# design.net
KiCad netlist of a schematic drawn in Altium Designer
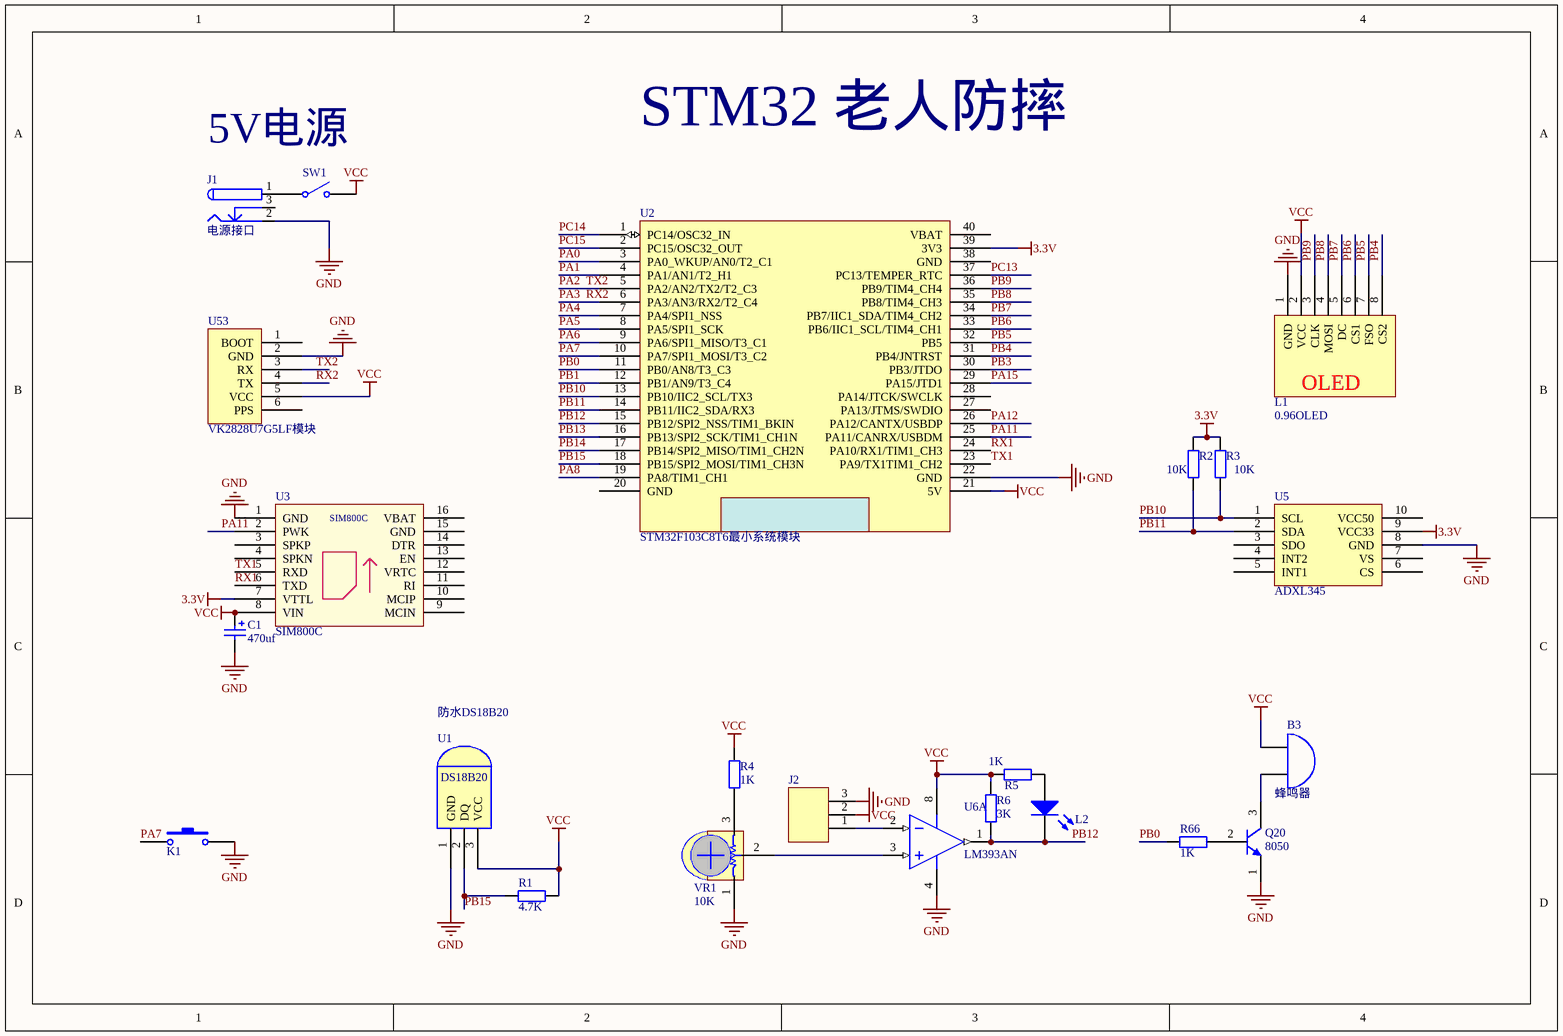
[diagram p0: 原理图.SchDoc]

(export (version "E")
  (design (tool "Eeschema 10.0.6"))
  (components
    (comp (ref "B3")
      (value "蜂鸣器")
      (footprint "Buzzy-Small")
      (description "Electrical Bell")
      (fields (field (name "PUBLISHER") "Altium Limited"))
      (libsource (lib "YANG") (part "Bell"))
    )
    (comp (ref "C1") (value "470uf") (footprint "CD5.08cm-10*16-M") (libsource (lib "电容") (part "Cap Pol")))
    (comp (ref "J1")
      (value "电源接口")
      (footprint "DC-JACK")
      (description "Low Voltage Power Supply Connector")
      (fields (field (name "PUBLISHER") "Altium Limited"))
      (libsource (lib "Miscellaneous Connectors") (part "PWR2.5"))
    )
    (comp (ref "J2") (value "~") (footprint "3ZHEN-100mil") (libsource (lib "元件") (part "H3")))
    (comp (ref "K1") (value "SW-AJ") (footprint "sw-6-6") (libsource (lib "YANG") (part "SW-AJ")))
    (comp (ref "L1") (value "0.96OLED") (footprint "OLED_0.96") (libsource (lib "万年历") (part "OLED_0.96")))
    (comp (ref "L2") (value "LED") (footprint "LED-3") (libsource (lib "YANG") (part "LED")))
    (comp (ref "Q20") (value "8050") (footprint "TO-92-2N3906") (libsource (lib "32") (part "8050")))
    (comp (ref "R1")
      (value "4.7K")
      (footprint "AXIAL-0.3")
      (description "Resistor")
      (libsource (lib "20170808毕业设计模块资料整理") (part "Res2"))
    )
    (comp (ref "R2") (value "10K") (footprint "AXIAL-0.3") (libsource (lib "YANG") (part "RES0.2")))
    (comp (ref "R3") (value "10K") (footprint "AXIAL-0.3") (libsource (lib "YANG") (part "RES0.2")))
    (comp (ref "R4")
      (value "1k")
      (footprint "AXIAL-0.3")
      (fields (field (name "ALTIUM_UNNAMED_1") "1K"))
      (libsource (lib "") (part "RES0.2_1"))
    )
    (comp (ref "R5") (value "1K") (footprint "AXIAL-0.3") (libsource (lib "YANG") (part "RES0.4")))
    (comp (ref "R6")
      (value "3k")
      (footprint "AXIAL-0.3")
      (fields (field (name "ALTIUM_UNNAMED_1") "3K"))
      (libsource (lib "") (part "RES0.2_1"))
    )
    (comp (ref "R66")
      (value "1K")
      (footprint "AXIAL-0.3")
      (description "Resistor")
      (libsource (lib "20170808毕业设计模块资料整理") (part "Res2"))
    )
    (comp (ref "SW1") (value "自锁开关") (footprint "SW1") (libsource (lib "各种开关") (part "SW-SPST")))
    (comp (ref "U1")
      (value "防水DS18B20")
      (footprint "DS18b20")
      (libsource (lib "20170808毕业设计模块资料整理") (part "DS18B20"))
    )
    (comp (ref "U2")
      (value "STM32F103C8T6最小系统模块")
      (footprint "STM32F103C8T6最下系统模块")
      (libsource (lib "32") (part "STM32F103C8T6最下系统模块"))
    )
    (comp (ref "U3") (value "SIM800C") (footprint "SIM800C") (libsource (lib "PCB_Project") (part "SIM800C")))
    (comp (ref "U5") (value "ADXL345") (footprint "ADXL345") (libsource (lib "原理图") (part "ADXL345")))
    (comp (ref "U6")
      (value "LM393AN")
      (footprint "DIP8")
      (description "Dual Comparator")
      (fields (field (name "PUBLISHER") "Altium Limited"))
      (libsource (lib "Motorola Analog Comparator") (part "LM393AN"))
    )
    (comp (ref "U53")
      (value "VK2828U7G5LF模块")
      (footprint "HDR1X6H")
      (libsource (lib "20170808毕业设计模块资料整理") (part "gps"))
    )
    (comp (ref "VR1")
      (value "10K")
      (footprint "W2")
      (libsource (lib "毕业设计模块资料SCH_Library. (1)") (part "电位器-蓝白"))
    )
  )
  (nets
    (net (code "1") (name "/PA0") (class "Default")
      (node (ref "U2") (pin "3") (pinfunction "PA0_WKUP/AN0/T2_C1_3") (pintype "passive"))
    )
    (net (code "2") (name "/PA1") (class "Default")
      (node (ref "U2") (pin "4") (pinfunction "PA1/AN1/T2_H1_4") (pintype "passive"))
    )
    (net (code "3") (name "/PA2") (class "Default")
      (node (ref "U2") (pin "5") (pinfunction "PA2/AN2/TX2/T2_C3_5") (pintype "passive"))
      (node (ref "U53") (pin "3") (pinfunction "RX_3") (pintype "passive"))
    )
    (net (code "4") (name "/PA3") (class "Default")
      (node (ref "U2") (pin "6") (pinfunction "PA3/AN3/RX2/T2_C4_6") (pintype "passive"))
      (node (ref "U53") (pin "4") (pinfunction "TX_4") (pintype "passive"))
    )
    (net (code "5") (name "/PA4") (class "Default")
      (node (ref "U2") (pin "7") (pinfunction "PA4/SPI1_NSS_7") (pintype "passive"))
    )
    (net (code "6") (name "/PA5") (class "Default")
      (node (ref "U2") (pin "8") (pinfunction "PA5/SPI1_SCK_8") (pintype "passive"))
    )
    (net (code "7") (name "/PA6") (class "Default")
      (node (ref "U2") (pin "9") (pinfunction "PA6/SPI1_MISO/T3_C1_9") (pintype "passive"))
    )
    (net (code "8") (name "/PA7") (class "Default")
      (node (ref "K1") (pin "1") (pinfunction "1_1") (pintype "passive"))
      (node (ref "U2") (pin "10") (pinfunction "PA7/SPI1_MOSI/T3_C2_10") (pintype "passive"))
    )
    (net (code "9") (name "/PA8") (class "Default")
      (node (ref "U2") (pin "19") (pinfunction "PA8/TIM1_CH1_19") (pintype "passive"))
    )
    (net (code "10") (name "/PA11") (class "Default")
      (node (ref "U2") (pin "25") (pinfunction "PA11/CANRX/USBDM_25") (pintype "passive"))
      (node (ref "U3") (pin "2") (pinfunction "PWK_2") (pintype "passive"))
    )
    (net (code "11") (name "/PA12") (class "Default")
      (node (ref "U2") (pin "26") (pinfunction "PA12/CANTX/USBDP_26") (pintype "passive"))
    )
    (net (code "12") (name "/PA15") (class "Default")
      (node (ref "U2") (pin "29") (pinfunction "PA15/JTD1_29") (pintype "passive"))
    )
    (net (code "13") (name "/PB0") (class "Default")
      (node (ref "R66") (pin "1") (pinfunction "1_1") (pintype "passive"))
      (node (ref "U2") (pin "11") (pinfunction "PB0/AN8/T3_C3_11") (pintype "passive"))
    )
    (net (code "14") (name "/PB1") (class "Default")
      (node (ref "U2") (pin "12") (pinfunction "PB1/AN9/T3_C4_12") (pintype "passive"))
    )
    (net (code "15") (name "/PB3") (class "Default")
      (node (ref "U2") (pin "30") (pinfunction "PB3/JTDO_30") (pintype "passive"))
    )
    (net (code "16") (name "/PB4") (class "Default")
      (node (ref "L1") (pin "8") (pinfunction "CS2_8") (pintype "passive"))
      (node (ref "U2") (pin "31") (pinfunction "PB4/JNTRST_31") (pintype "passive"))
    )
    (net (code "17") (name "/PB5") (class "Default")
      (node (ref "L1") (pin "7") (pinfunction "FSO_7") (pintype "passive"))
      (node (ref "U2") (pin "32") (pinfunction "PB5_32") (pintype "passive"))
    )
    (net (code "18") (name "/PB6") (class "Default")
      (node (ref "L1") (pin "6") (pinfunction "CS1_6") (pintype "passive"))
      (node (ref "U2") (pin "33") (pinfunction "PB6/IIC1_SCL/TIM4_CH1_33") (pintype "passive"))
    )
    (net (code "19") (name "/PB7") (class "Default")
      (node (ref "L1") (pin "5") (pinfunction "DC_5") (pintype "passive"))
      (node (ref "U2") (pin "34") (pinfunction "PB7/IIC1_SDA/TIM4_CH2_34") (pintype "passive"))
    )
    (net (code "20") (name "/PB8") (class "Default")
      (node (ref "L1") (pin "4") (pinfunction "MOSI_4") (pintype "passive"))
      (node (ref "U2") (pin "35") (pinfunction "PB8/TIM4_CH3_35") (pintype "passive"))
    )
    (net (code "21") (name "/PB9") (class "Default")
      (node (ref "L1") (pin "3") (pinfunction "CLK_3") (pintype "passive"))
      (node (ref "U2") (pin "36") (pinfunction "PB9/TIM4_CH4_36") (pintype "passive"))
    )
    (net (code "22") (name "/PB10") (class "Default")
      (node (ref "R3") (pin "1") (pinfunction "1_1") (pintype "passive"))
      (node (ref "U2") (pin "13") (pinfunction "PB10/IIC2_SCL/TX3_13") (pintype "passive"))
      (node (ref "U5") (pin "1") (pinfunction "SCL_1") (pintype "passive"))
    )
    (net (code "23") (name "/PB11") (class "Default")
      (node (ref "R2") (pin "1") (pinfunction "1_1") (pintype "passive"))
      (node (ref "U2") (pin "14") (pinfunction "PB11/IIC2_SDA/RX3_14") (pintype "passive"))
      (node (ref "U5") (pin "2") (pinfunction "SDA_2") (pintype "passive"))
    )
    (net (code "24") (name "/PB12") (class "Default")
      (node (ref "L2") (pin "2") (pinfunction "K_2") (pintype "passive"))
      (node (ref "R6") (pin "2") (pinfunction "2_2") (pintype "passive"))
      (node (ref "U2") (pin "15") (pinfunction "PB12/SPI2_NSS/TIM1_BKIN_15") (pintype "passive"))
      (node (ref "U6") (pin "1") (pinfunction "OUT_1") (pintype "output"))
    )
    (net (code "25") (name "/PB13") (class "Default")
      (node (ref "U2") (pin "16") (pinfunction "PB13/SPI2_SCK/TIM1_CH1N_16") (pintype "passive"))
    )
    (net (code "26") (name "/PB14") (class "Default")
      (node (ref "U2") (pin "17") (pinfunction "PB14/SPI2_MISO/TIM1_CH2N_17") (pintype "passive"))
    )
    (net (code "27") (name "/PB15") (class "Default")
      (node (ref "R1") (pin "1") (pinfunction "1_1") (pintype "passive"))
      (node (ref "U1") (pin "2") (pinfunction "DQ_2") (pintype "passive"))
      (node (ref "U2") (pin "18") (pinfunction "PB15/SPI2_MOSI/TIM1_CH3N_18") (pintype "passive"))
    )
    (net (code "28") (name "/PC13") (class "Default")
      (node (ref "U2") (pin "37") (pinfunction "PC13/TEMPER_RTC_37") (pintype "passive"))
    )
    (net (code "29") (name "/PC14") (class "Default")
      (node (ref "U2") (pin "1") (pinfunction "PC14/OSC32_IN_1") (pintype "bidirectional"))
    )
    (net (code "30") (name "/PC15") (class "Default")
      (node (ref "U2") (pin "2") (pinfunction "PC15/OSC32_OUT_2") (pintype "passive"))
    )
    (net (code "31") (name "/RX1") (class "Default")
      (node (ref "U2") (pin "24") (pinfunction "PA10/RX1/TIM1_CH3_24") (pintype "passive"))
      (node (ref "U3") (pin "6") (pinfunction "TXD_6") (pintype "passive"))
    )
    (net (code "32") (name "/TX1") (class "Default")
      (node (ref "U2") (pin "23") (pinfunction "PA9/TX1TIM1_CH2_23") (pintype "passive"))
      (node (ref "U3") (pin "5") (pinfunction "RXD_5") (pintype "passive"))
    )
    (net (code "33") (name "3.3V") (class "Default")
      (node (ref "R2") (pin "2") (pinfunction "2_2") (pintype "passive"))
      (node (ref "R3") (pin "2") (pinfunction "2_2") (pintype "passive"))
      (node (ref "U2") (pin "39") (pinfunction "3V3_39") (pintype "passive"))
      (node (ref "U3") (pin "7") (pinfunction "VTTL_7") (pintype "passive"))
      (node (ref "U5") (pin "9") (pinfunction "VCC33_9") (pintype "passive"))
    )
    (net (code "34") (name "GND") (class "Default")
      (node (ref "C1") (pin "2") (pinfunction "2_2") (pintype "passive"))
      (node (ref "J1") (pin "2") (pinfunction "2_2") (pintype "power_in"))
      (node (ref "J2") (pin "3") (pinfunction "3_3") (pintype "passive"))
      (node (ref "K1") (pin "2") (pinfunction "2_2") (pintype "passive"))
      (node (ref "L1") (pin "1") (pinfunction "GND_1") (pintype "passive"))
      (node (ref "Q20") (pin "1") (pinfunction "E_1") (pintype "passive"))
      (node (ref "U1") (pin "1") (pinfunction "GND_1") (pintype "passive"))
      (node (ref "U2") (pin "22") (pinfunction "GND_22") (pintype "passive"))
      (node (ref "U3") (pin "1") (pinfunction "GND_1") (pintype "passive"))
      (node (ref "U5") (pin "8") (pinfunction "GND_8") (pintype "passive"))
      (node (ref "U53") (pin "2") (pinfunction "GND_2") (pintype "passive"))
      (node (ref "U6") (pin "4") (pinfunction "GND_4") (pintype "power_in"))
      (node (ref "VR1") (pin "1") (pinfunction "1_1") (pintype "passive"))
    )
    (net (code "35") (name "Net-(B3-B)") (class "Default")
      (node (ref "B3") (pin "2") (pinfunction "B_2") (pintype "passive"))
      (node (ref "Q20") (pin "3") (pinfunction "C_3") (pintype "passive"))
    )
    (net (code "36") (name "Net-(L2-A)") (class "Default")
      (node (ref "L2") (pin "1") (pinfunction "A_1") (pintype "passive"))
      (node (ref "R5") (pin "2") (pinfunction "2_2") (pintype "passive"))
    )
    (net (code "37") (name "Net-(Q20-B)") (class "Default")
      (node (ref "Q20") (pin "2") (pinfunction "B_2") (pintype "passive"))
      (node (ref "R66") (pin "2") (pinfunction "2_2") (pintype "passive"))
    )
    (net (code "38") (name "Net-(R4-Pad2)") (class "Default")
      (node (ref "R4") (pin "2") (pinfunction "2_2") (pintype "passive"))
      (node (ref "VR1") (pin "3") (pinfunction "3_3") (pintype "passive"))
    )
    (net (code "39") (name "Net-(SW1-COMMON)") (class "Default")
      (node (ref "J1") (pin "1") (pinfunction "1_1") (pintype "power_in"))
      (node (ref "SW1") (pin "1") (pinfunction "COMMON_1") (pintype "passive"))
    )
    (net (code "40") (name "Net-(U6A-IN+)") (class "Default")
      (node (ref "U6") (pin "3") (pinfunction "IN+_3") (pintype "input"))
      (node (ref "VR1") (pin "2") (pinfunction "2_2") (pintype "passive"))
    )
    (net (code "41") (name "Net-(U6A-IN-)") (class "Default")
      (node (ref "J2") (pin "1") (pinfunction "1_1") (pintype "passive"))
      (node (ref "U6") (pin "2") (pinfunction "IN-_2") (pintype "input"))
    )
    (net (code "42") (name "VCC") (class "Default")
      (node (ref "B3") (pin "1") (pinfunction "A_1") (pintype "passive"))
      (node (ref "C1") (pin "1") (pinfunction "1_1") (pintype "passive"))
      (node (ref "J2") (pin "2") (pinfunction "2_2") (pintype "passive"))
      (node (ref "L1") (pin "2") (pinfunction "VCC_2") (pintype "passive"))
      (node (ref "R1") (pin "2") (pinfunction "2_2") (pintype "passive"))
      (node (ref "R4") (pin "1") (pinfunction "1_1") (pintype "passive"))
      (node (ref "R5") (pin "1") (pinfunction "1_1") (pintype "passive"))
      (node (ref "R6") (pin "1") (pinfunction "1_1") (pintype "passive"))
      (node (ref "SW1") (pin "2") (pinfunction "NO_2") (pintype "passive"))
      (node (ref "U1") (pin "3") (pinfunction "VCC_3") (pintype "passive"))
      (node (ref "U2") (pin "21") (pinfunction "5V_21") (pintype "passive"))
      (node (ref "U3") (pin "8") (pinfunction "VIN_8") (pintype "passive"))
      (node (ref "U53") (pin "5") (pinfunction "VCC_5") (pintype "passive"))
      (node (ref "U6") (pin "8") (pinfunction "V+_8") (pintype "power_in"))
    )
    (net (code "43") (name "unconnected-(J1-Pad3)") (class "Default")
      (node (ref "J1") (pin "3") (pinfunction "3_3") (pintype "power_in"))
    )
    (net (code "44") (name "unconnected-(U2-GND-Pad20)") (class "Default")
      (node (ref "U2") (pin "20") (pinfunction "GND_20") (pintype "passive"))
    )
    (net (code "45") (name "unconnected-(U2-GND-Pad38)") (class "Default")
      (node (ref "U2") (pin "38") (pinfunction "GND_38") (pintype "passive"))
    )
    (net (code "46") (name "unconnected-(U2-PA13{slash}JTMS{slash}SWDIO-Pad27)") (class "Default")
      (node (ref "U2") (pin "27") (pinfunction "PA13/JTMS/SWDIO_27") (pintype "passive"))
    )
    (net (code "47") (name "unconnected-(U2-PA14{slash}JTCK{slash}SWCLK-Pad28)") (class "Default")
      (node (ref "U2") (pin "28") (pinfunction "PA14/JTCK/SWCLK_28") (pintype "passive"))
    )
    (net (code "48") (name "unconnected-(U2-VBAT-Pad40)") (class "Default")
      (node (ref "U2") (pin "40") (pinfunction "VBAT_40") (pintype "passive"))
    )
    (net (code "49") (name "unconnected-(U3-DTR-Pad14)") (class "Default")
      (node (ref "U3") (pin "14") (pinfunction "DTR_14") (pintype "passive"))
    )
    (net (code "50") (name "unconnected-(U3-EN-Pad13)") (class "Default")
      (node (ref "U3") (pin "13") (pinfunction "EN_13") (pintype "passive"))
    )
    (net (code "51") (name "unconnected-(U3-GND-Pad15)") (class "Default")
      (node (ref "U3") (pin "15") (pinfunction "GND_15") (pintype "passive"))
    )
    (net (code "52") (name "unconnected-(U3-MCIN-Pad9)") (class "Default")
      (node (ref "U3") (pin "9") (pinfunction "MCIN_9") (pintype "passive"))
    )
    (net (code "53") (name "unconnected-(U3-MCIP-Pad10)") (class "Default")
      (node (ref "U3") (pin "10") (pinfunction "MCIP_10") (pintype "passive"))
    )
    (net (code "54") (name "unconnected-(U3-RI-Pad11)") (class "Default")
      (node (ref "U3") (pin "11") (pinfunction "RI_11") (pintype "passive"))
    )
    (net (code "55") (name "unconnected-(U3-SPKN-Pad4)") (class "Default")
      (node (ref "U3") (pin "4") (pinfunction "SPKN_4") (pintype "passive"))
    )
    (net (code "56") (name "unconnected-(U3-SPKP-Pad3)") (class "Default")
      (node (ref "U3") (pin "3") (pinfunction "SPKP_3") (pintype "passive"))
    )
    (net (code "57") (name "unconnected-(U3-VBAT-Pad16)") (class "Default")
      (node (ref "U3") (pin "16") (pinfunction "VBAT_16") (pintype "passive"))
    )
    (net (code "58") (name "unconnected-(U3-VRTC-Pad12)") (class "Default")
      (node (ref "U3") (pin "12") (pinfunction "VRTC_12") (pintype "passive"))
    )
    (net (code "59") (name "unconnected-(U5-CS-Pad6)") (class "Default")
      (node (ref "U5") (pin "6") (pinfunction "CS_6") (pintype "passive"))
    )
    (net (code "60") (name "unconnected-(U5-INT1-Pad5)") (class "Default")
      (node (ref "U5") (pin "5") (pinfunction "INT1_5") (pintype "passive"))
    )
    (net (code "61") (name "unconnected-(U5-INT2-Pad4)") (class "Default")
      (node (ref "U5") (pin "4") (pinfunction "INT2_4") (pintype "passive"))
    )
    (net (code "62") (name "unconnected-(U5-SDO-Pad3)") (class "Default")
      (node (ref "U5") (pin "3") (pinfunction "SDO_3") (pintype "passive"))
    )
    (net (code "63") (name "unconnected-(U5-VCC50-Pad10)") (class "Default")
      (node (ref "U5") (pin "10") (pinfunction "VCC50_10") (pintype "passive"))
    )
    (net (code "64") (name "unconnected-(U5-VS-Pad7)") (class "Default")
      (node (ref "U5") (pin "7") (pinfunction "VS_7") (pintype "passive"))
    )
    (net (code "65") (name "unconnected-(U53-BOOT-Pad1)") (class "Default")
      (node (ref "U53") (pin "1") (pinfunction "BOOT_1") (pintype "passive"))
    )
    (net (code "66") (name "unconnected-(U53-PPS-Pad6)") (class "Default")
      (node (ref "U53") (pin "6") (pinfunction "PPS_6") (pintype "passive"))
    )
  )
)
